# cp32m4_wrover.net
KiCad netlist of a schematic drawn in EAGLE
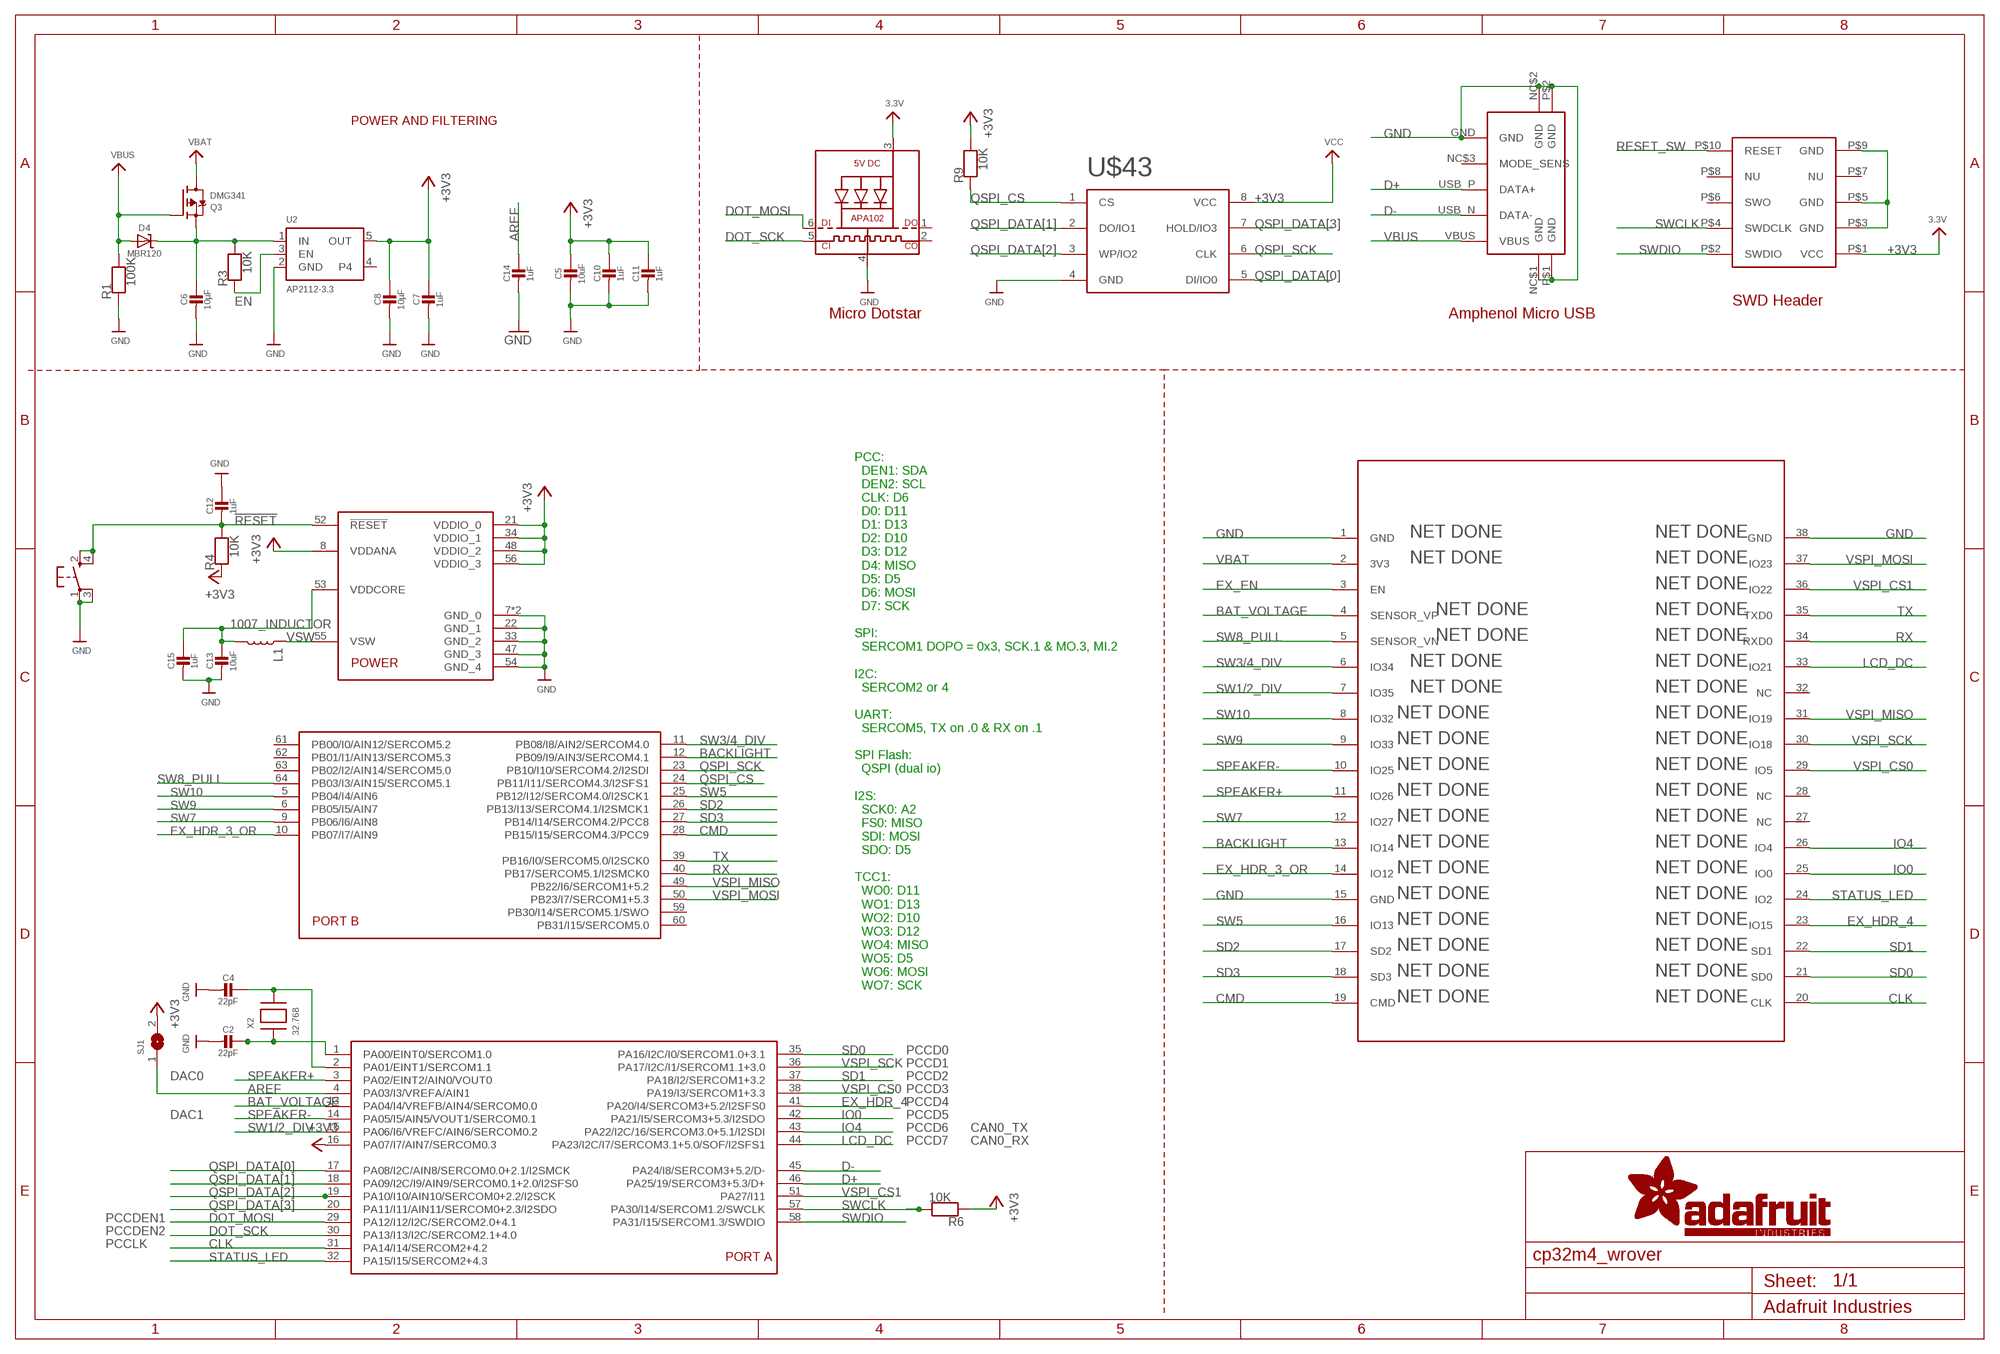
[diagram p0: schematic, sheet 1]

(export (version "E")
  (design (tool "Eeschema 10.0.6"))
  (components
    (comp (ref "C2")
      (value "22pF")
      (footprint "eagle-import:0603-NO")
      (libsource (lib "eagle-import") (part "CAP_CERAMIC0603_NO"))
    )
    (comp (ref "C4")
      (value "22pF")
      (footprint "eagle-import:0603-NO")
      (libsource (lib "eagle-import") (part "CAP_CERAMIC0603_NO"))
    )
    (comp (ref "C5")
      (value "10uF")
      (footprint "eagle-import:0805-NO")
      (libsource (lib "eagle-import") (part "CAP_CERAMIC0805-NOOUTLINE"))
    )
    (comp (ref "C6")
      (value "10µF")
      (footprint "eagle-import:0805-NO")
      (libsource (lib "eagle-import") (part "CAP_CERAMIC0805-NOOUTLINE"))
    )
    (comp (ref "C7")
      (value "1uF")
      (footprint "eagle-import:0603-NO")
      (libsource (lib "eagle-import") (part "CAP_CERAMIC0603_NO"))
    )
    (comp (ref "C8")
      (value "10µF")
      (footprint "eagle-import:0805-NO")
      (libsource (lib "eagle-import") (part "CAP_CERAMIC0805-NOOUTLINE"))
    )
    (comp (ref "C10")
      (value "1uF")
      (footprint "eagle-import:0603-NO")
      (libsource (lib "eagle-import") (part "CAP_CERAMIC0603_NO"))
    )
    (comp (ref "C11")
      (value "1uF")
      (footprint "eagle-import:0603-NO")
      (libsource (lib "eagle-import") (part "CAP_CERAMIC0603_NO"))
    )
    (comp (ref "C12")
      (value "1uF")
      (footprint "eagle-import:0603-NO")
      (libsource (lib "eagle-import") (part "CAP_CERAMIC0603_NO"))
    )
    (comp (ref "C13")
      (value "10uF")
      (footprint "eagle-import:0805-NO")
      (libsource (lib "eagle-import") (part "CAP_CERAMIC0805-NOOUTLINE"))
    )
    (comp (ref "C14")
      (value "1uF")
      (footprint "eagle-import:0603-NO")
      (libsource (lib "eagle-import") (part "CAP_CERAMIC0603_NO"))
    )
    (comp (ref "C15")
      (value "1uF")
      (footprint "eagle-import:0603-NO")
      (libsource (lib "eagle-import") (part "CAP_CERAMIC0603_NO"))
    )
    (comp (ref "D4")
      (value "MBR120")
      (footprint "eagle-import:SOD-123")
      (libsource (lib "eagle-import") (part "DIODE-SCHOTTKYSOD-123"))
    )
    (comp (ref "L1")
      (value "1007_INDUCTOR")
      (footprint "eagle-import:1007_INDUCTOR")
      (libsource (lib "eagle-import") (part "1007_INDUCTOR"))
    )
    (comp (ref "LED2")
      (value "AP102-2020")
      (footprint "eagle-import:APA102_2020")
      (libsource (lib "eagle-import") (part "APA1022020"))
    )
    (comp (ref "Q3")
      (value "DMG341")
      (footprint "eagle-import:SOT23-R")
      (libsource (lib "eagle-import") (part "MOSFET-P"))
    )
    (comp (ref "R1")
      (value "100K")
      (footprint "eagle-import:0603-NO")
      (libsource (lib "eagle-import") (part "RESISTOR_0603_NOOUT"))
    )
    (comp (ref "R3")
      (value "10K")
      (footprint "eagle-import:0603-NO")
      (libsource (lib "eagle-import") (part "RESISTOR_0603_NOOUT"))
    )
    (comp (ref "R4")
      (value "10K")
      (footprint "eagle-import:0603-NO")
      (libsource (lib "eagle-import") (part "RESISTOR_0603_NOOUT"))
    )
    (comp (ref "R6")
      (value "10K")
      (footprint "eagle-import:0603-NO")
      (libsource (lib "eagle-import") (part "RESISTOR_0603_NOOUT"))
    )
    (comp (ref "R9")
      (value "10K")
      (footprint "eagle-import:0603-NO")
      (libsource (lib "eagle-import") (part "RESISTOR_0603_NOOUT"))
    )
    (comp (ref "SJ1")
      (value "SOLDERJUMPERCLOSED")
      (footprint "eagle-import:SOLDERJUMPER_CLOSEDWIRE")
      (libsource (lib "eagle-import") (part "SOLDERJUMPERCLOSED"))
    )
    (comp (ref "SW1")
      (value "SPST_TACT-KMR2")
      (footprint "eagle-import:KMR2")
      (libsource (lib "eagle-import") (part "SPST_TACT-KMR2"))
    )
    (comp (ref "U$7")
      (value "ESP32_WROVER")
      (footprint "eagle-import:ESP32_WROVER")
      (libsource (lib "eagle-import") (part "ESP32_WROVER"))
    )
    (comp (ref "U$14")
      (value "ATSAMD51J")
      (footprint "eagle-import:PQFN64-1")
      (libsource (lib "eagle-import") (part "ATSAMD51J"))
    )
    (comp (ref "U$43")
      (value "WINDBOND_QSPI_FLASHWSON_6X5")
      (footprint "eagle-import:WSON_6X5MM")
      (libsource (lib "eagle-import") (part "WINDBOND_QSPI_FLASHWSON_6X5"))
    )
    (comp (ref "U$44")
      (value "SWD_HEADER")
      (footprint "eagle-import:AMPHENOL_SWD")
      (libsource (lib "eagle-import") (part "SWD_HEADER"))
    )
    (comp (ref "U$50")
      (value "AMPHENOL_MICRO_USBAMPHENOL_MICRO_USB_BETTER")
      (footprint "eagle-import:BETTER_AMP_MICRO_USB")
      (libsource (lib "eagle-import") (part "AMPHENOL_MICRO_USBAMPHENOL_MICRO_USB_BETTER"))
    )
    (comp (ref "U2")
      (value "AP2112-3.3")
      (footprint "eagle-import:SOT23-5")
      (libsource (lib "eagle-import") (part "VREG_SOT23-5"))
    )
    (comp (ref "X2")
      (value "32.768")
      (footprint "eagle-import:XTAL3215")
      (libsource (lib "eagle-import") (part "XTAL-3.2X1.5"))
    )
  )
  (nets
    (net (code "1") (name "+3V3") (class "Default")
      (node (ref "C10") (pin "1") (pinfunction "1_1") (pintype "passive"))
      (node (ref "C11") (pin "1") (pinfunction "1_1") (pintype "passive"))
      (node (ref "C5") (pin "1") (pinfunction "1_1") (pintype "passive"))
      (node (ref "C7") (pin "1") (pinfunction "1_1") (pintype "passive"))
      (node (ref "C8") (pin "1") (pinfunction "1_1") (pintype "passive"))
      (node (ref "LED2") (pin "3") (pinfunction "VDD_3") (pintype "power_in"))
      (node (ref "R4") (pin "1") (pinfunction "1_1") (pintype "passive"))
      (node (ref "R6") (pin "1") (pinfunction "1_1") (pintype "passive"))
      (node (ref "R9") (pin "2") (pinfunction "2_2") (pintype "passive"))
      (node (ref "SJ1") (pin "2") (pinfunction "2_2") (pintype "passive"))
      (node (ref "U$14") (pin "16") (pinfunction "PA07/I7/AIN7/SERCOM0.3_16") (pintype "bidirectional"))
      (node (ref "U$14") (pin "21") (pinfunction "VDDIO_0_21") (pintype "bidirectional"))
      (node (ref "U$14") (pin "34") (pinfunction "VDDIO_1_34") (pintype "bidirectional"))
      (node (ref "U$14") (pin "48") (pinfunction "VDDIO_2_48") (pintype "bidirectional"))
      (node (ref "U$14") (pin "56") (pinfunction "VDDIO_3_56") (pintype "bidirectional"))
      (node (ref "U$14") (pin "8") (pinfunction "VDDANA_8") (pintype "bidirectional"))
      (node (ref "U$43") (pin "8") (pinfunction "VCC_8") (pintype "passive"))
      (node (ref "U$44") (pin "P$1") (pinfunction "VCC_P$1") (pintype "bidirectional"))
      (node (ref "U2") (pin "5") (pinfunction "OUT_5") (pintype "power_in"))
    )
    (net (code "2") (name "/AREF") (class "Default")
      (node (ref "C14") (pin "1") (pinfunction "1_1") (pintype "passive"))
      (node (ref "SJ1") (pin "1") (pinfunction "1_1") (pintype "passive"))
      (node (ref "U$14") (pin "4") (pinfunction "PA03/I3/VREFA/AIN1_4") (pintype "bidirectional"))
    )
    (net (code "3") (name "/BACKLIGHT") (class "Default")
      (node (ref "U$14") (pin "12") (pinfunction "PB09/I9/AIN3/SERCOM4.1_12") (pintype "bidirectional"))
      (node (ref "U$7") (pin "13") (pinfunction "IO14_13") (pintype "bidirectional"))
    )
    (net (code "4") (name "/BAT_VOLTAGE") (class "Default")
      (node (ref "U$14") (pin "13") (pinfunction "PA04/I4/VREFB/AIN4/SERCOM0.0_13") (pintype "bidirectional"))
      (node (ref "U$7") (pin "4") (pinfunction "SENSOR_VP_4") (pintype "bidirectional"))
    )
    (net (code "5") (name "/CLK") (class "Default")
      (node (ref "U$14") (pin "31") (pinfunction "PA14/I14/SERCOM2+4.2_31") (pintype "bidirectional"))
      (node (ref "U$7") (pin "20") (pinfunction "CLK_20") (pintype "bidirectional"))
    )
    (net (code "6") (name "/CMD") (class "Default")
      (node (ref "U$14") (pin "28") (pinfunction "PB15/I15/SERCOM4.3/PCC9_28") (pintype "bidirectional"))
      (node (ref "U$7") (pin "19") (pinfunction "CMD_19") (pintype "bidirectional"))
    )
    (net (code "7") (name "/D+") (class "Default")
      (node (ref "U$14") (pin "46") (pinfunction "PA25/19/SERCOM3+5.3/D+_46") (pintype "bidirectional"))
      (node (ref "U$50") (pin "USB_P") (pinfunction "DATA+_USB_P") (pintype "bidirectional"))
    )
    (net (code "8") (name "/D-") (class "Default")
      (node (ref "U$14") (pin "45") (pinfunction "PA24/I8/SERCOM3+5.2/D-_45") (pintype "bidirectional"))
      (node (ref "U$50") (pin "USB_N") (pinfunction "DATA-_USB_N") (pintype "bidirectional"))
    )
    (net (code "9") (name "/DOT_MOSI") (class "Default")
      (node (ref "LED2") (pin "6") (pinfunction "DI_6") (pintype "input"))
      (node (ref "U$14") (pin "29") (pinfunction "PA12/I12/I2C/SERCOM2.0+4.1_29") (pintype "bidirectional"))
    )
    (net (code "10") (name "/DOT_SCK") (class "Default")
      (node (ref "LED2") (pin "5") (pinfunction "CKI_5") (pintype "input"))
      (node (ref "U$14") (pin "30") (pinfunction "PA13/I13/I2C/SERCOM2.1+4.0_30") (pintype "bidirectional"))
    )
    (net (code "11") (name "/EN") (class "Default")
      (node (ref "R3") (pin "1") (pinfunction "1_1") (pintype "passive"))
      (node (ref "U2") (pin "3") (pinfunction "EN_3") (pintype "input"))
    )
    (net (code "12") (name "/EX_EN") (class "Default")
      (node (ref "U$7") (pin "3") (pinfunction "EN_3") (pintype "bidirectional"))
    )
    (net (code "13") (name "/EX_HDR_3_OR") (class "Default")
      (node (ref "U$14") (pin "10") (pinfunction "PB07/I7/AIN9_10") (pintype "bidirectional"))
      (node (ref "U$7") (pin "14") (pinfunction "IO12_14") (pintype "bidirectional"))
    )
    (net (code "14") (name "/EX_HDR_4") (class "Default")
      (node (ref "U$14") (pin "41") (pinfunction "PA20/I4/SERCOM3+5.2/I2SFS0_41") (pintype "bidirectional"))
      (node (ref "U$7") (pin "23") (pinfunction "IO15_23") (pintype "bidirectional"))
    )
    (net (code "15") (name "/IO0") (class "Default")
      (node (ref "U$14") (pin "42") (pinfunction "PA21/I5/SERCOM3+5.3/I2SDO_42") (pintype "bidirectional"))
      (node (ref "U$7") (pin "25") (pinfunction "IO0_25") (pintype "bidirectional"))
    )
    (net (code "16") (name "/IO4") (class "Default")
      (node (ref "U$14") (pin "43") (pinfunction "PA22/I2C/16/SERCOM3.0+5.1/I2SDI_43") (pintype "bidirectional"))
      (node (ref "U$7") (pin "26") (pinfunction "IO4_26") (pintype "bidirectional"))
    )
    (net (code "17") (name "/LCD_DC") (class "Default")
      (node (ref "U$14") (pin "44") (pinfunction "PA23/I2C/I7/SERCOM3.1+5.0/SOF/I2SFS1_44") (pintype "bidirectional"))
      (node (ref "U$7") (pin "33") (pinfunction "IO21_33") (pintype "bidirectional"))
    )
    (net (code "18") (name "/QSPI_CS") (class "Default")
      (node (ref "R9") (pin "1") (pinfunction "1_1") (pintype "passive"))
      (node (ref "U$14") (pin "24") (pinfunction "PB11/I11/SERCOM4.3/I2SFS1_24") (pintype "bidirectional"))
      (node (ref "U$43") (pin "1") (pinfunction "CS_1") (pintype "bidirectional"))
    )
    (net (code "19") (name "/QSPI_DATA[0]") (class "Default")
      (node (ref "U$14") (pin "17") (pinfunction "PA08/I2C/AIN8/SERCOM0.0+2.1/I2SMCK_17") (pintype "bidirectional"))
      (node (ref "U$43") (pin "5") (pinfunction "DI/IO0_5") (pintype "bidirectional"))
    )
    (net (code "20") (name "/QSPI_DATA[1]") (class "Default")
      (node (ref "U$14") (pin "18") (pinfunction "PA09/I2C/I9/AIN9/SERCOM0.1+2.0/I2SFS0_18") (pintype "bidirectional"))
      (node (ref "U$43") (pin "2") (pinfunction "DO/IO1_2") (pintype "bidirectional"))
    )
    (net (code "21") (name "/QSPI_DATA[2]") (class "Default")
      (node (ref "U$14") (pin "19") (pinfunction "PA10/I10/AIN10/SERCOM0+2.2/I2SCK_19") (pintype "bidirectional"))
      (node (ref "U$43") (pin "3") (pinfunction "WP/IO2_3") (pintype "bidirectional"))
    )
    (net (code "22") (name "/QSPI_DATA[3]") (class "Default")
      (node (ref "U$14") (pin "20") (pinfunction "PA11/I11/AIN11/SERCOM0+2.3/I2SDO_20") (pintype "bidirectional"))
      (node (ref "U$43") (pin "7") (pinfunction "HOLD/IO3_7") (pintype "bidirectional"))
    )
    (net (code "23") (name "/QSPI_SCK") (class "Default")
      (node (ref "U$14") (pin "23") (pinfunction "PB10/I10/SERCOM4.2/I2SDI_23") (pintype "bidirectional"))
      (node (ref "U$43") (pin "6") (pinfunction "CLK_6") (pintype "bidirectional"))
    )
    (net (code "24") (name "/RESET_SW") (class "Default")
      (node (ref "U$44") (pin "P$10") (pinfunction "RESET_P$10") (pintype "bidirectional"))
    )
    (net (code "25") (name "/RX") (class "Default")
      (node (ref "U$14") (pin "40") (pinfunction "PB17/SERCOM5.1/I2SMCK0_40") (pintype "bidirectional"))
      (node (ref "U$7") (pin "34") (pinfunction "RXD0_34") (pintype "bidirectional"))
    )
    (net (code "26") (name "/SD0") (class "Default")
      (node (ref "U$14") (pin "35") (pinfunction "PA16/I2C/I0/SERCOM1.0+3.1_35") (pintype "bidirectional"))
      (node (ref "U$7") (pin "21") (pinfunction "SD0_21") (pintype "bidirectional"))
    )
    (net (code "27") (name "/SD1") (class "Default")
      (node (ref "U$14") (pin "37") (pinfunction "PA18/I2/SERCOM1+3.2_37") (pintype "bidirectional"))
      (node (ref "U$7") (pin "22") (pinfunction "SD1_22") (pintype "bidirectional"))
    )
    (net (code "28") (name "/SD2") (class "Default")
      (node (ref "U$14") (pin "26") (pinfunction "PB13/I13/SERCOM4.1/I2SMCK1_26") (pintype "bidirectional"))
      (node (ref "U$7") (pin "17") (pinfunction "SD2_17") (pintype "bidirectional"))
    )
    (net (code "29") (name "/SD3") (class "Default")
      (node (ref "U$14") (pin "27") (pinfunction "PB14/I14/SERCOM4.2/PCC8_27") (pintype "bidirectional"))
      (node (ref "U$7") (pin "18") (pinfunction "SD3_18") (pintype "bidirectional"))
    )
    (net (code "30") (name "/SPEAKER+") (class "Default")
      (node (ref "U$14") (pin "3") (pinfunction "PA02/EINT2/AIN0/VOUT0_3") (pintype "bidirectional"))
      (node (ref "U$7") (pin "11") (pinfunction "IO26_11") (pintype "bidirectional"))
    )
    (net (code "31") (name "/SPEAKER-") (class "Default")
      (node (ref "U$14") (pin "14") (pinfunction "PA05/I5/AIN5/VOUT1/SERCOM0.1_14") (pintype "bidirectional"))
      (node (ref "U$7") (pin "10") (pinfunction "IO25_10") (pintype "bidirectional"))
    )
    (net (code "32") (name "/STATUS_LED") (class "Default")
      (node (ref "U$14") (pin "32") (pinfunction "PA15/I15/SERCOM2+4.3_32") (pintype "bidirectional"))
      (node (ref "U$7") (pin "24") (pinfunction "IO2_24") (pintype "bidirectional"))
    )
    (net (code "33") (name "/SW1{slash}2_DIV") (class "Default")
      (node (ref "U$14") (pin "15") (pinfunction "PA06/I6/VREFC/AIN6/SERCOM0.2_15") (pintype "bidirectional"))
      (node (ref "U$7") (pin "7") (pinfunction "IO35_7") (pintype "bidirectional"))
    )
    (net (code "34") (name "/SW3{slash}4_DIV") (class "Default")
      (node (ref "U$14") (pin "11") (pinfunction "PB08/I8/AIN2/SERCOM4.0_11") (pintype "bidirectional"))
      (node (ref "U$7") (pin "6") (pinfunction "IO34_6") (pintype "bidirectional"))
    )
    (net (code "35") (name "/SW5") (class "Default")
      (node (ref "U$14") (pin "25") (pinfunction "PB12/I12/SERCOM4.0/I2SCK1_25") (pintype "bidirectional"))
      (node (ref "U$7") (pin "16") (pinfunction "IO13_16") (pintype "bidirectional"))
    )
    (net (code "36") (name "/SW7") (class "Default")
      (node (ref "U$14") (pin "9") (pinfunction "PB06/I6/AIN8_9") (pintype "bidirectional"))
      (node (ref "U$7") (pin "12") (pinfunction "IO27_12") (pintype "bidirectional"))
    )
    (net (code "37") (name "/SW8_PULL") (class "Default")
      (node (ref "U$14") (pin "64") (pinfunction "PB03/I3/AIN15/SERCOM5.1_64") (pintype "bidirectional"))
      (node (ref "U$7") (pin "5") (pinfunction "SENSOR_VN_5") (pintype "bidirectional"))
    )
    (net (code "38") (name "/SW9") (class "Default")
      (node (ref "U$14") (pin "6") (pinfunction "PB05/I5/AIN7_6") (pintype "bidirectional"))
      (node (ref "U$7") (pin "9") (pinfunction "IO33_9") (pintype "bidirectional"))
    )
    (net (code "39") (name "/SW10") (class "Default")
      (node (ref "U$14") (pin "5") (pinfunction "PB04/I4/AIN6_5") (pintype "bidirectional"))
      (node (ref "U$7") (pin "8") (pinfunction "IO32_8") (pintype "bidirectional"))
    )
    (net (code "40") (name "/SWCLK") (class "Default")
      (node (ref "R6") (pin "2") (pinfunction "2_2") (pintype "passive"))
      (node (ref "U$14") (pin "57") (pinfunction "PA30/I14/SERCOM1.2/SWCLK_57") (pintype "bidirectional"))
      (node (ref "U$44") (pin "P$4") (pinfunction "SWDCLK_P$4") (pintype "bidirectional"))
    )
    (net (code "41") (name "/SWDIO") (class "Default")
      (node (ref "U$14") (pin "58") (pinfunction "PA31/I15/SERCOM1.3/SWDIO_58") (pintype "bidirectional"))
      (node (ref "U$44") (pin "P$2") (pinfunction "SWDIO_P$2") (pintype "bidirectional"))
    )
    (net (code "42") (name "/TX") (class "Default")
      (node (ref "U$14") (pin "39") (pinfunction "PB16/I0/SERCOM5.0/I2SCK0_39") (pintype "bidirectional"))
      (node (ref "U$7") (pin "35") (pinfunction "TXD0_35") (pintype "bidirectional"))
    )
    (net (code "43") (name "/VSPI_CS0") (class "Default")
      (node (ref "U$14") (pin "38") (pinfunction "PA19/I3/SERCOM1+3.3_38") (pintype "bidirectional"))
      (node (ref "U$7") (pin "29") (pinfunction "IO5_29") (pintype "bidirectional"))
    )
    (net (code "44") (name "/VSPI_CS1") (class "Default")
      (node (ref "U$14") (pin "51") (pinfunction "PA27/I11_51") (pintype "bidirectional"))
      (node (ref "U$7") (pin "36") (pinfunction "IO22_36") (pintype "bidirectional"))
    )
    (net (code "45") (name "/VSPI_MISO") (class "Default")
      (node (ref "U$14") (pin "49") (pinfunction "PB22/I6/SERCOM1+5.2_49") (pintype "bidirectional"))
      (node (ref "U$7") (pin "31") (pinfunction "IO19_31") (pintype "bidirectional"))
    )
    (net (code "46") (name "/VSPI_MOSI") (class "Default")
      (node (ref "U$14") (pin "50") (pinfunction "PB23/I7/SERCOM1+5.3_50") (pintype "bidirectional"))
      (node (ref "U$7") (pin "37") (pinfunction "IO23_37") (pintype "bidirectional"))
    )
    (net (code "47") (name "/VSPI_SCK") (class "Default")
      (node (ref "U$14") (pin "36") (pinfunction "PA17/I2C/I1/SERCOM1.1+3.0_36") (pintype "bidirectional"))
      (node (ref "U$7") (pin "30") (pinfunction "IO18_30") (pintype "bidirectional"))
    )
    (net (code "48") (name "/VSW") (class "Default")
      (node (ref "L1") (pin "P$1") (pinfunction "1_P$1") (pintype "passive"))
      (node (ref "U$14") (pin "55") (pinfunction "VSW_55") (pintype "bidirectional"))
    )
    (net (code "49") (name "/~{RESET}") (class "Default")
      (node (ref "C12") (pin "2") (pinfunction "2_2") (pintype "passive"))
      (node (ref "R4") (pin "2") (pinfunction "2_2") (pintype "passive"))
      (node (ref "SW1") (pin "2") (pinfunction "S_2") (pintype "passive"))
      (node (ref "SW1") (pin "4") (pinfunction "S1_4") (pintype "passive"))
      (node (ref "U$14") (pin "52") (pinfunction "~{RESET}_52") (pintype "bidirectional"))
    )
    (net (code "50") (name "GND") (class "Default")
      (node (ref "C10") (pin "2") (pinfunction "2_2") (pintype "passive"))
      (node (ref "C11") (pin "2") (pinfunction "2_2") (pintype "passive"))
      (node (ref "C12") (pin "1") (pinfunction "1_1") (pintype "passive"))
      (node (ref "C13") (pin "2") (pinfunction "2_2") (pintype "passive"))
      (node (ref "C14") (pin "2") (pinfunction "2_2") (pintype "passive"))
      (node (ref "C15") (pin "2") (pinfunction "2_2") (pintype "passive"))
      (node (ref "C2") (pin "2") (pinfunction "2_2") (pintype "passive"))
      (node (ref "C4") (pin "2") (pinfunction "2_2") (pintype "passive"))
      (node (ref "C5") (pin "2") (pinfunction "2_2") (pintype "passive"))
      (node (ref "C6") (pin "2") (pinfunction "2_2") (pintype "passive"))
      (node (ref "C7") (pin "2") (pinfunction "2_2") (pintype "passive"))
      (node (ref "C8") (pin "2") (pinfunction "2_2") (pintype "passive"))
      (node (ref "LED2") (pin "4") (pinfunction "GND_4") (pintype "power_in"))
      (node (ref "R1") (pin "1") (pinfunction "1_1") (pintype "passive"))
      (node (ref "SW1") (pin "1") (pinfunction "P_1") (pintype "passive"))
      (node (ref "SW1") (pin "3") (pinfunction "P1_3") (pintype "passive"))
      (node (ref "U$14") (pin "22") (pinfunction "GND_1_22") (pintype "bidirectional"))
      (node (ref "U$14") (pin "33") (pinfunction "GND_2_33") (pintype "bidirectional"))
      (node (ref "U$14") (pin "47") (pinfunction "GND_3_47") (pintype "bidirectional"))
      (node (ref "U$14") (pin "54") (pinfunction "GND_4_54") (pintype "bidirectional"))
      (node (ref "U$14") (pin "7") (pinfunction "GND_0_7") (pintype "bidirectional"))
      (node (ref "U$14") (pin "EXP") (pinfunction "GND_0_EXP") (pintype "bidirectional"))
      (node (ref "U$43") (pin "4") (pinfunction "GND_4") (pintype "power_in"))
      (node (ref "U$44") (pin "P$3") (pinfunction "GND_P$3") (pintype "bidirectional"))
      (node (ref "U$44") (pin "P$5") (pinfunction "GND_P$5") (pintype "bidirectional"))
      (node (ref "U$44") (pin "P$9") (pinfunction "GND_P$9") (pintype "bidirectional"))
      (node (ref "U$50") (pin "GND") (pinfunction "GND_GND") (pintype "bidirectional"))
      (node (ref "U$50") (pin "NC$1") (pinfunction "GND_NC$1") (pintype "bidirectional"))
      (node (ref "U$50") (pin "NC$2") (pinfunction "GND_NC$2") (pintype "bidirectional"))
      (node (ref "U$50") (pin "P$1") (pinfunction "GND_P$1") (pintype "bidirectional"))
      (node (ref "U$50") (pin "P$2") (pinfunction "GND_P$2") (pintype "bidirectional"))
      (node (ref "U$7") (pin "1") (pinfunction "GND_1") (pintype "power_in"))
      (node (ref "U$7") (pin "15") (pinfunction "GND_15") (pintype "power_in"))
      (node (ref "U$7") (pin "38") (pinfunction "GND_38") (pintype "power_in"))
      (node (ref "U2") (pin "2") (pinfunction "GND_2") (pintype "power_in"))
    )
    (net (code "51") (name "Net-(L1-2)") (class "Default")
      (node (ref "C13") (pin "1") (pinfunction "1_1") (pintype "passive"))
      (node (ref "C15") (pin "1") (pinfunction "1_1") (pintype "passive"))
      (node (ref "L1") (pin "P$2") (pinfunction "2_P$2") (pintype "passive"))
      (node (ref "U$14") (pin "53") (pinfunction "VDDCORE_53") (pintype "bidirectional"))
    )
    (net (code "52") (name "Net-(Q3-S)") (class "Default")
      (node (ref "C6") (pin "1") (pinfunction "1_1") (pintype "passive"))
      (node (ref "D4") (pin "C") (pinfunction "C_C") (pintype "passive"))
      (node (ref "Q3") (pin "2") (pinfunction "S_2") (pintype "passive"))
      (node (ref "R3") (pin "2") (pinfunction "2_2") (pintype "passive"))
      (node (ref "U2") (pin "1") (pinfunction "IN_1") (pintype "power_in"))
    )
    (net (code "53") (name "Net-(U$14A-PA00{slash}EINT0{slash}SERCOM1.0)") (class "Default")
      (node (ref "C2") (pin "1") (pinfunction "1_1") (pintype "passive"))
      (node (ref "U$14") (pin "1") (pinfunction "PA00/EINT0/SERCOM1.0_1") (pintype "bidirectional"))
      (node (ref "X2") (pin "P$1") (pinfunction "P$1_P$1") (pintype "bidirectional"))
    )
    (net (code "54") (name "Net-(U$14A-PA01{slash}EINT1{slash}SERCOM1.1)") (class "Default")
      (node (ref "C4") (pin "1") (pinfunction "1_1") (pintype "passive"))
      (node (ref "U$14") (pin "2") (pinfunction "PA01/EINT1/SERCOM1.1_2") (pintype "bidirectional"))
      (node (ref "X2") (pin "P$2") (pinfunction "P$2_P$2") (pintype "bidirectional"))
    )
    (net (code "55") (name "VBAT") (class "Default")
      (node (ref "Q3") (pin "3") (pinfunction "D_3") (pintype "passive"))
      (node (ref "U$7") (pin "2") (pinfunction "3V3_2") (pintype "power_in"))
    )
    (net (code "56") (name "VBUS") (class "Default")
      (node (ref "D4") (pin "A") (pinfunction "A_A") (pintype "passive"))
      (node (ref "Q3") (pin "1") (pinfunction "G_1") (pintype "passive"))
      (node (ref "R1") (pin "2") (pinfunction "2_2") (pintype "passive"))
      (node (ref "U$50") (pin "VBUS") (pinfunction "VBUS_VBUS") (pintype "bidirectional"))
    )
    (net (code "57") (name "unconnected-(LED2-CKO-Pad2)") (class "Default")
      (node (ref "LED2") (pin "2") (pinfunction "CKO_2") (pintype "output"))
    )
    (net (code "58") (name "unconnected-(LED2-DO-Pad1)") (class "Default")
      (node (ref "LED2") (pin "1") (pinfunction "DO_1") (pintype "output"))
    )
    (net (code "59") (name "unconnected-(U$7-NC-Pad27)") (class "Default")
      (node (ref "U$7") (pin "27") (pinfunction "NC_27") (pintype "input"))
    )
    (net (code "60") (name "unconnected-(U$7-NC-Pad28)") (class "Default")
      (node (ref "U$7") (pin "28") (pinfunction "NC_28") (pintype "no_connect"))
    )
    (net (code "61") (name "unconnected-(U$7-NC-Pad32)") (class "Default")
      (node (ref "U$7") (pin "32") (pinfunction "NC_32") (pintype "no_connect"))
    )
    (net (code "62") (name "unconnected-(U$14B-PB00{slash}I0{slash}AIN12{slash}SERCOM5.2-Pad61)") (class "Default")
      (node (ref "U$14") (pin "61") (pinfunction "PB00/I0/AIN12/SERCOM5.2_61") (pintype "bidirectional"))
    )
    (net (code "63") (name "unconnected-(U$14B-PB01{slash}I1{slash}AIN13{slash}SERCOM5.3-Pad62)") (class "Default")
      (node (ref "U$14") (pin "62") (pinfunction "PB01/I1/AIN13/SERCOM5.3_62") (pintype "bidirectional"))
    )
    (net (code "64") (name "unconnected-(U$14B-PB02{slash}I2{slash}AIN14{slash}SERCOM5.0-Pad63)") (class "Default")
      (node (ref "U$14") (pin "63") (pinfunction "PB02/I2/AIN14/SERCOM5.0_63") (pintype "bidirectional"))
    )
    (net (code "65") (name "unconnected-(U$14B-PB30{slash}I14{slash}SERCOM5.1{slash}SWO-Pad59)") (class "Default")
      (node (ref "U$14") (pin "59") (pinfunction "PB30/I14/SERCOM5.1/SWO_59") (pintype "bidirectional"))
    )
    (net (code "66") (name "unconnected-(U$14B-PB31{slash}I15{slash}SERCOM5.0-Pad60)") (class "Default")
      (node (ref "U$14") (pin "60") (pinfunction "PB31/I15/SERCOM5.0_60") (pintype "bidirectional"))
    )
    (net (code "67") (name "unconnected-(U$44-NU-PadP$7)") (class "Default")
      (node (ref "U$44") (pin "P$7") (pinfunction "NU_P$7") (pintype "bidirectional"))
    )
    (net (code "68") (name "unconnected-(U$44-NU-PadP$8)") (class "Default")
      (node (ref "U$44") (pin "P$8") (pinfunction "NU_P$8") (pintype "bidirectional"))
    )
    (net (code "69") (name "unconnected-(U$44-SWO-PadP$6)") (class "Default")
      (node (ref "U$44") (pin "P$6") (pinfunction "SWO_P$6") (pintype "bidirectional"))
    )
    (net (code "70") (name "unconnected-(U$50-MODE_SENS-PadNC$3)") (class "Default")
      (node (ref "U$50") (pin "NC$3") (pinfunction "MODE_SENS_NC$3") (pintype "bidirectional"))
    )
    (net (code "71") (name "unconnected-(U2-P4-Pad4)") (class "Default")
      (node (ref "U2") (pin "4") (pinfunction "P4_4") (pintype "bidirectional"))
    )
  )
)
